# RHD2000_128_headstage.net
KiCad netlist of a schematic drawn in EAGLE
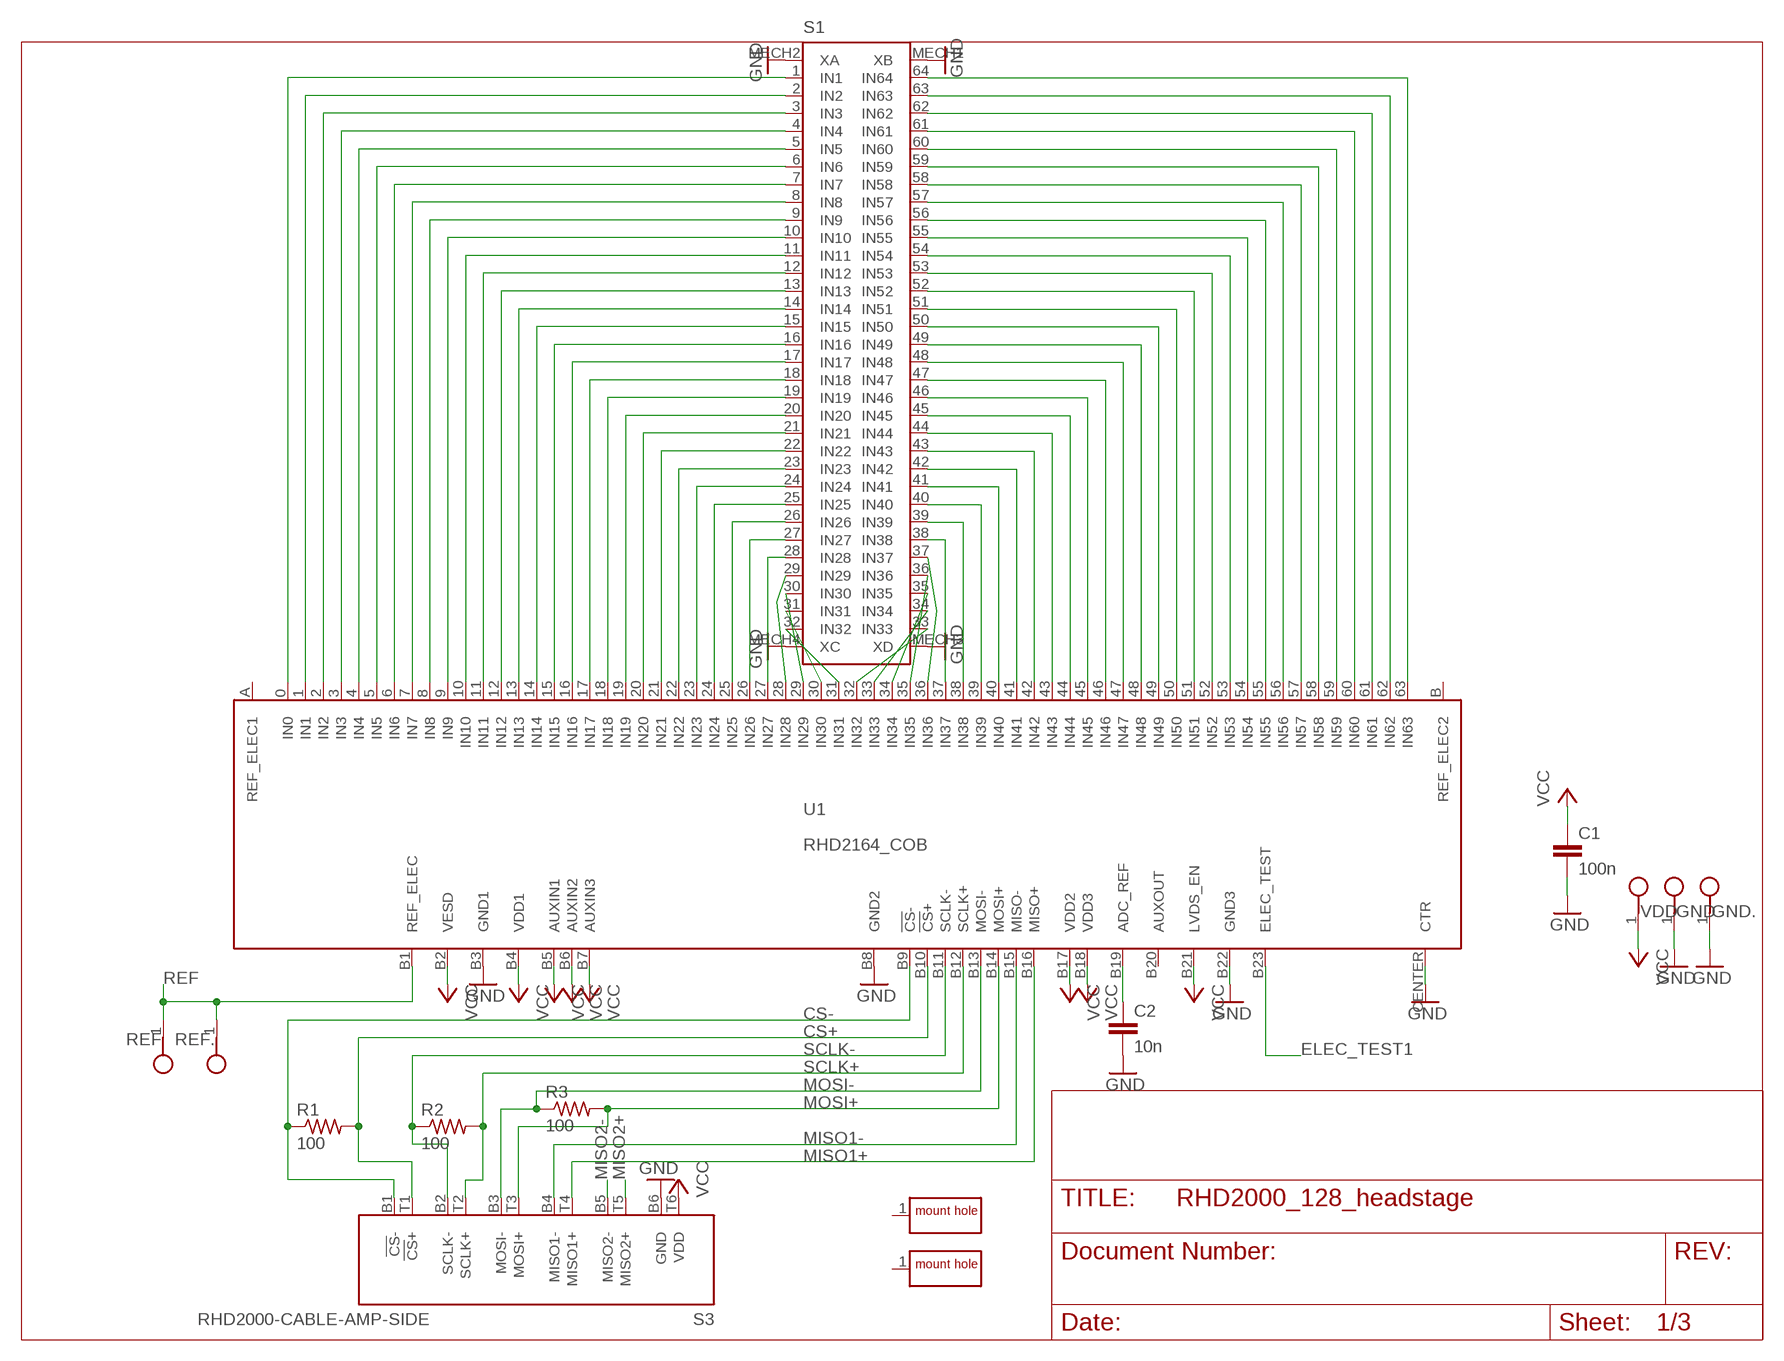
[diagram p0: schematic, sheet 1]
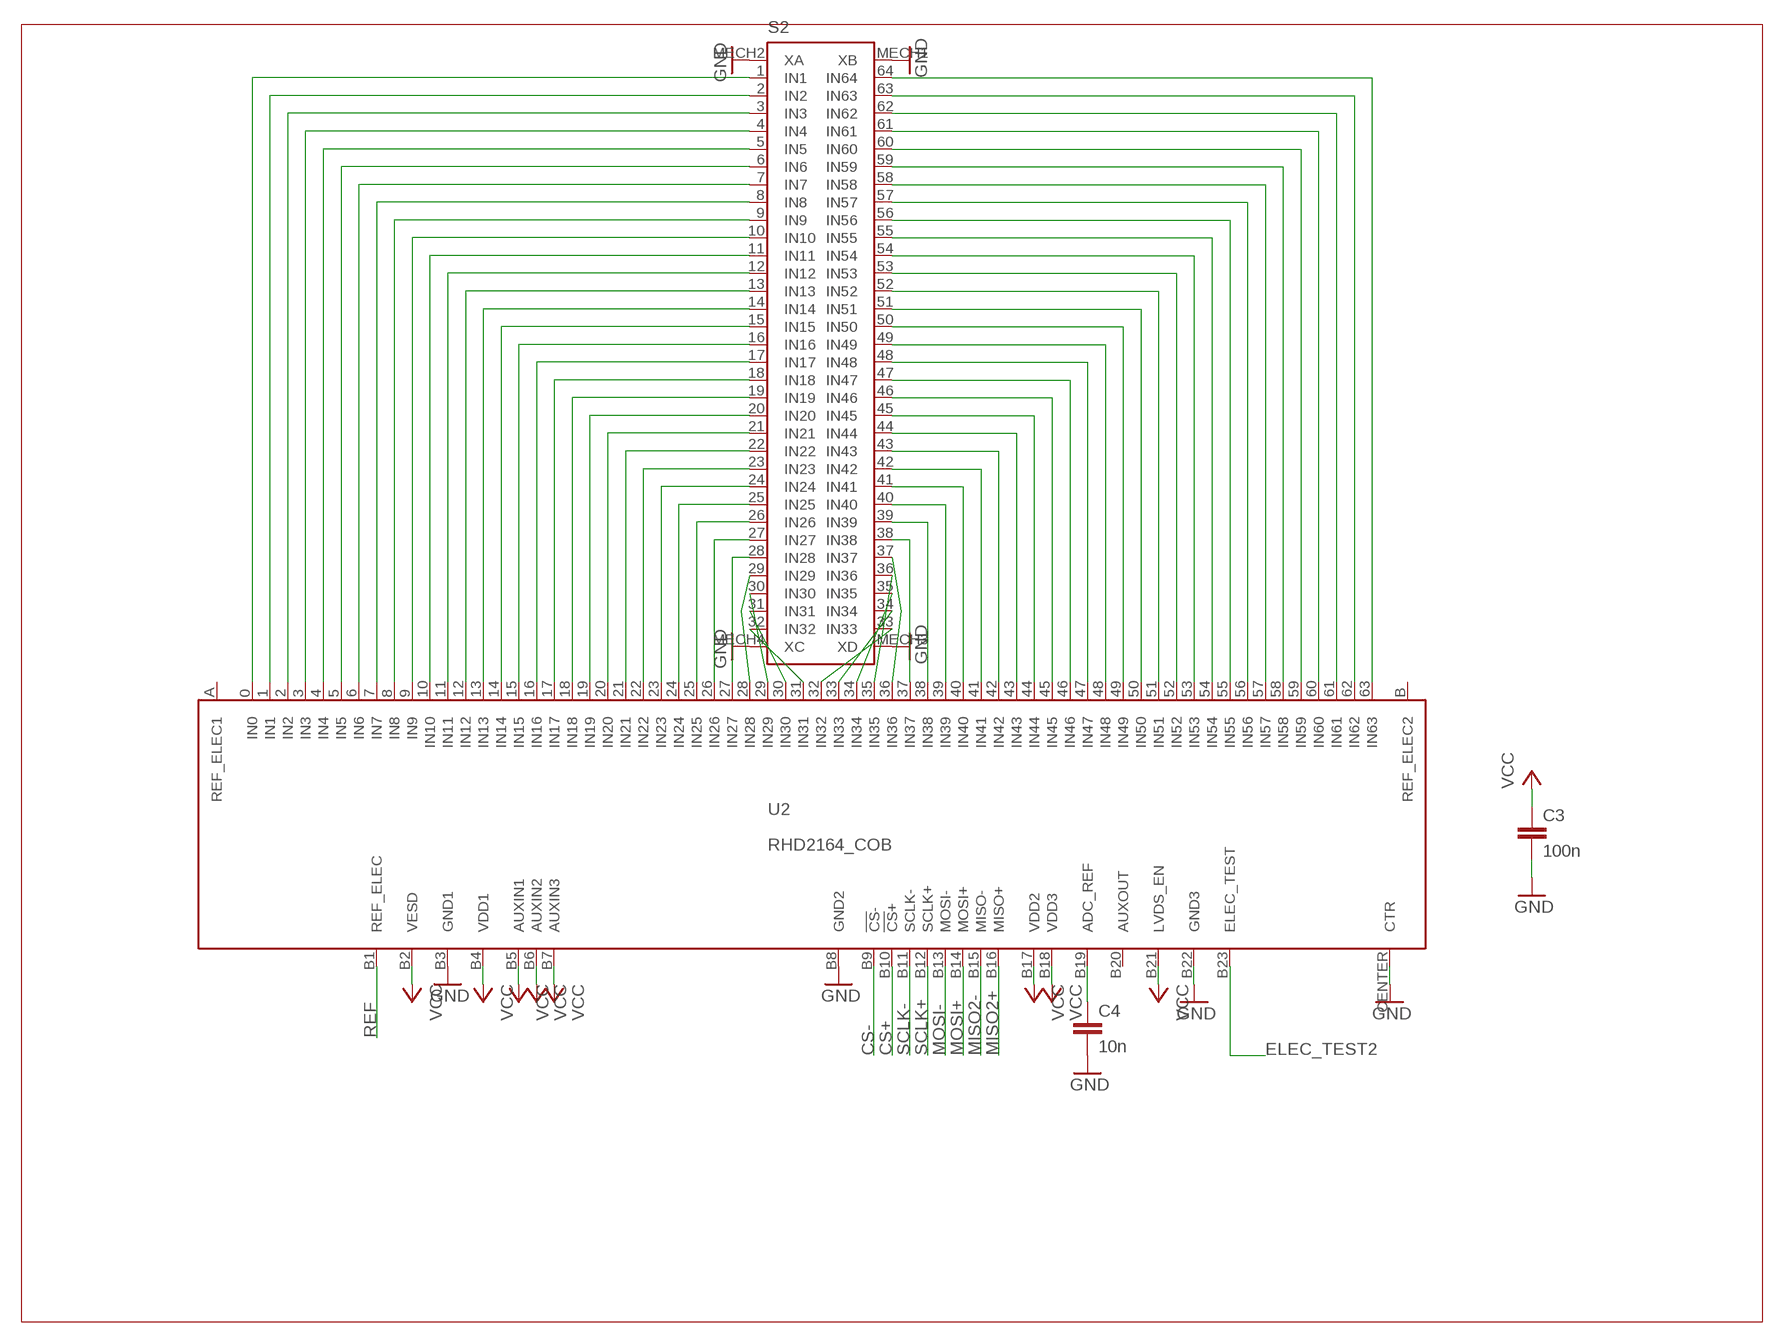
[diagram p1: schematic, sheet 2]
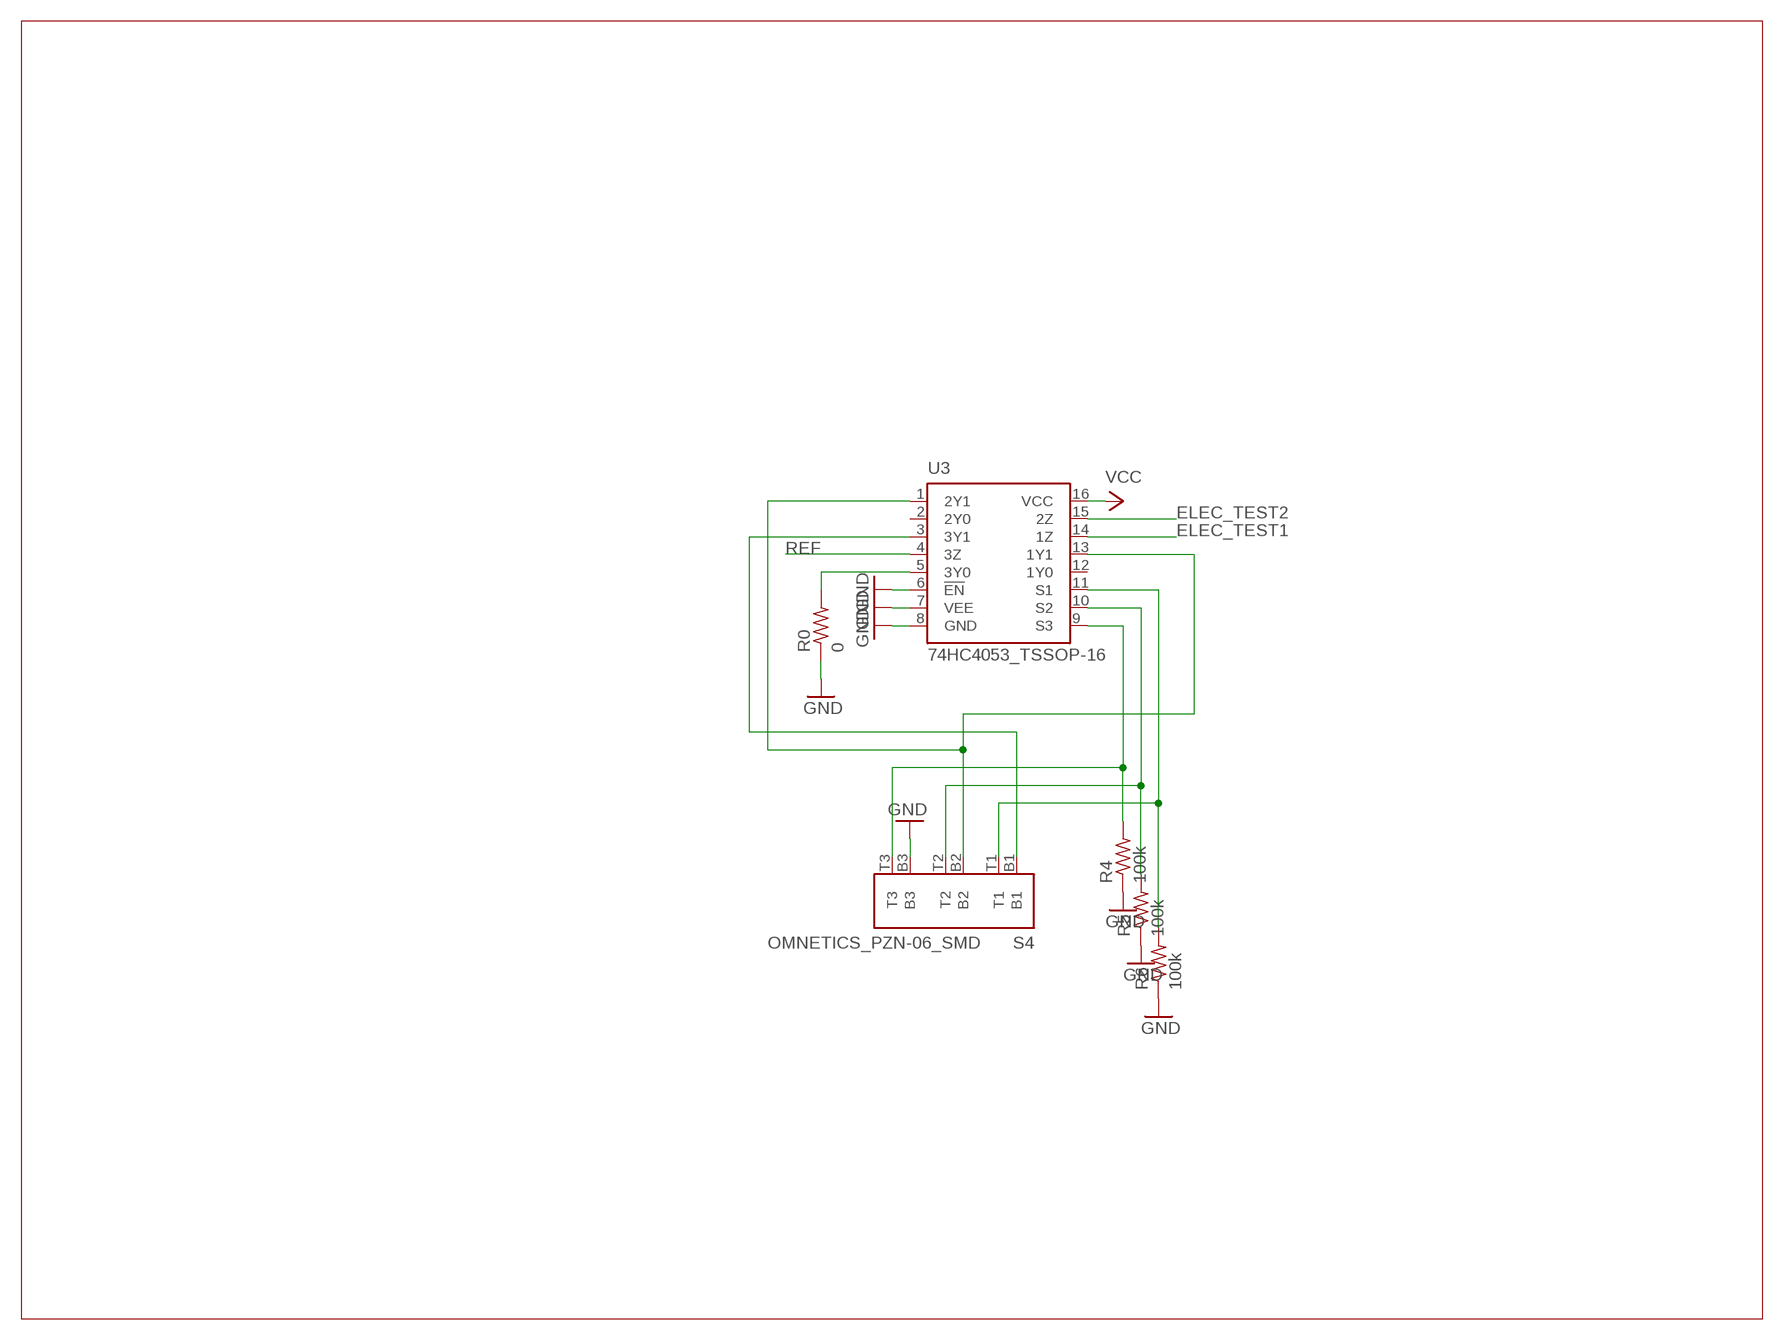
[diagram p2: schematic, sheet 3]

(export (version "E")
  (design (tool "Eeschema 10.0.6"))
  (components
    (comp (ref "C1")
      (value "100n")
      (footprint "eagle-import:0402")
      (libsource (lib "eagle-import") (part "C_0402"))
    )
    (comp (ref "C2")
      (value "10n")
      (footprint "eagle-import:0201")
      (libsource (lib "eagle-import") (part "C_0201"))
    )
    (comp (ref "GND")
      (value "TESTPOINT_SMALL")
      (footprint "eagle-import:TESTPOINT_SMALL")
      (libsource (lib "eagle-import") (part "TESTPOINT_SMALL"))
    )
    (comp (ref "GND.")
      (value "TESTPOINT_SMALL")
      (footprint "eagle-import:TESTPOINT_SMALL")
      (libsource (lib "eagle-import") (part "TESTPOINT_SMALL"))
    )
    (comp (ref "H1")
      (value "MOUNTING_HOLE_60MIL")
      (footprint "eagle-import:MOUNTING_HOLE_60MIL")
      (libsource (lib "eagle-import") (part "MOUNTING_HOLE_60MIL"))
    )
    (comp (ref "H2")
      (value "MOUNTING_HOLE_60MIL")
      (footprint "eagle-import:MOUNTING_HOLE_60MIL")
      (libsource (lib "eagle-import") (part "MOUNTING_HOLE_60MIL"))
    )
    (comp (ref "R1")
      (value "100")
      (footprint "eagle-import:0201")
      (libsource (lib "eagle-import") (part "R_0201"))
    )
    (comp (ref "R2")
      (value "100")
      (footprint "eagle-import:0201")
      (libsource (lib "eagle-import") (part "R_0201"))
    )
    (comp (ref "R3")
      (value "100")
      (footprint "eagle-import:0201")
      (libsource (lib "eagle-import") (part "R_0201"))
    )
    (comp (ref "REF")
      (value "TESTPOINT_SMALL")
      (footprint "eagle-import:TESTPOINT_SMALL")
      (libsource (lib "eagle-import") (part "TESTPOINT_SMALL"))
    )
    (comp (ref "REF.")
      (value "TESTPOINT_SMALL")
      (footprint "eagle-import:TESTPOINT_SMALL")
      (libsource (lib "eagle-import") (part "TESTPOINT_SMALL"))
    )
    (comp (ref "S1")
      (value "MOLEX_SLIMSTACK_64")
      (footprint "eagle-import:MOLEX_SLIMSTACK_64")
      (libsource (lib "eagle-import") (part "MOLEX_SLIMSTACK_64"))
    )
    (comp (ref "S3")
      (value "RHD2000-CABLE-AMP-SIDE")
      (footprint "eagle-import:OMNETICS_PZN-12-AA")
      (libsource (lib "eagle-import") (part "RHD2000-CABLE-AMP-SIDE"))
    )
    (comp (ref "U1")
      (value "RHD2164_COB")
      (footprint "eagle-import:RHD2164_COB")
      (libsource (lib "eagle-import") (part "RHD2164_COB"))
    )
    (comp (ref "VDD")
      (value "TESTPOINT_SMALL")
      (footprint "eagle-import:TESTPOINT_SMALL")
      (libsource (lib "eagle-import") (part "TESTPOINT_SMALL"))
    )
    (comp (ref "R0")
      (value "0")
      (footprint "eagle-import:0402")
      (libsource (lib "eagle-import") (part "R_0402"))
    )
    (comp (ref "R4")
      (value "100k")
      (footprint "eagle-import:0201")
      (libsource (lib "eagle-import") (part "R_0201"))
    )
    (comp (ref "R5")
      (value "100k")
      (footprint "eagle-import:0201")
      (libsource (lib "eagle-import") (part "R_0201"))
    )
    (comp (ref "R6")
      (value "100k")
      (footprint "eagle-import:0201")
      (libsource (lib "eagle-import") (part "R_0201"))
    )
    (comp (ref "S4")
      (value "OMNETICS_PZN-06_SMD")
      (footprint "eagle-import:OMNETICS_PZN-06-AA")
      (libsource (lib "eagle-import") (part "OMNETICS_PZN-06_SMD"))
    )
    (comp (ref "U3")
      (value "74HC4053_TSSOP-16")
      (footprint "eagle-import:TSSOP-16")
      (libsource (lib "eagle-import") (part "74HC4053_TSSOP-16"))
    )
    (comp (ref "C3")
      (value "100n")
      (footprint "eagle-import:0402")
      (libsource (lib "eagle-import") (part "C_0402"))
    )
    (comp (ref "C4")
      (value "10n")
      (footprint "eagle-import:0201")
      (libsource (lib "eagle-import") (part "C_0201"))
    )
    (comp (ref "S2")
      (value "MOLEX_SLIMSTACK_64")
      (footprint "eagle-import:MOLEX_SLIMSTACK_64")
      (libsource (lib "eagle-import") (part "MOLEX_SLIMSTACK_64"))
    )
    (comp (ref "U2")
      (value "RHD2164_COB")
      (footprint "eagle-import:RHD2164_COB")
      (libsource (lib "eagle-import") (part "RHD2164_COB"))
    )
  )
  (nets
    (net (code "1") (name "CS+") (class "Default")
      (node (ref "R1") (pin "2") (pinfunction "2_2") (pintype "passive"))
      (node (ref "S3") (pin "T1") (pinfunction "~{CS}+_T1") (pintype "bidirectional"))
      (node (ref "U1") (pin "B10") (pinfunction "~{CS}+_B10") (pintype "input"))
      (node (ref "U2") (pin "B10") (pinfunction "~{CS}+_B10") (pintype "input"))
    )
    (net (code "2") (name "CS-") (class "Default")
      (node (ref "R1") (pin "1") (pinfunction "1_1") (pintype "passive"))
      (node (ref "S3") (pin "B1") (pinfunction "~{CS}-_B1") (pintype "bidirectional"))
      (node (ref "U1") (pin "B9") (pinfunction "~{CS}-_B9") (pintype "input"))
      (node (ref "U2") (pin "B9") (pinfunction "~{CS}-_B9") (pintype "input"))
    )
    (net (code "3") (name "ELEC_TEST1") (class "Default")
      (node (ref "U1") (pin "B23") (pinfunction "ELEC_TEST_B23") (pintype "input"))
      (node (ref "U3") (pin "14") (pinfunction "1Z_14") (pintype "bidirectional"))
    )
    (net (code "4") (name "ELEC_TEST2") (class "Default")
      (node (ref "U2") (pin "B23") (pinfunction "ELEC_TEST_B23") (pintype "input"))
      (node (ref "U3") (pin "15") (pinfunction "2Z_15") (pintype "bidirectional"))
    )
    (net (code "5") (name "GND") (class "Default")
      (node (ref "C1") (pin "2") (pinfunction "2_2") (pintype "passive"))
      (node (ref "C2") (pin "2") (pinfunction "2_2") (pintype "passive"))
      (node (ref "C3") (pin "2") (pinfunction "2_2") (pintype "passive"))
      (node (ref "C4") (pin "2") (pinfunction "2_2") (pintype "passive"))
      (node (ref "GND") (pin "1") (pinfunction "1_1") (pintype "passive"))
      (node (ref "GND.") (pin "1") (pinfunction "1_1") (pintype "passive"))
      (node (ref "R0") (pin "1") (pinfunction "1_1") (pintype "passive"))
      (node (ref "R4") (pin "1") (pinfunction "1_1") (pintype "passive"))
      (node (ref "R5") (pin "1") (pinfunction "1_1") (pintype "passive"))
      (node (ref "R6") (pin "1") (pinfunction "1_1") (pintype "passive"))
      (node (ref "S1") (pin "MECH1") (pinfunction "XB_MECH1") (pintype "input"))
      (node (ref "S1") (pin "MECH2") (pinfunction "XA_MECH2") (pintype "input"))
      (node (ref "S1") (pin "MECH3") (pinfunction "XD_MECH3") (pintype "input"))
      (node (ref "S1") (pin "MECH4") (pinfunction "XC_MECH4") (pintype "input"))
      (node (ref "S2") (pin "MECH1") (pinfunction "XB_MECH1") (pintype "input"))
      (node (ref "S2") (pin "MECH2") (pinfunction "XA_MECH2") (pintype "input"))
      (node (ref "S2") (pin "MECH3") (pinfunction "XD_MECH3") (pintype "input"))
      (node (ref "S2") (pin "MECH4") (pinfunction "XC_MECH4") (pintype "input"))
      (node (ref "S3") (pin "B6") (pinfunction "GND_B6") (pintype "power_in"))
      (node (ref "S4") (pin "B3") (pinfunction "B3_B3") (pintype "bidirectional"))
      (node (ref "U1") (pin "B22") (pinfunction "GND3_B22") (pintype "power_in"))
      (node (ref "U1") (pin "B3") (pinfunction "GND1_B3") (pintype "power_in"))
      (node (ref "U1") (pin "B8") (pinfunction "GND2_B8") (pintype "power_in"))
      (node (ref "U1") (pin "CENTER") (pinfunction "CTR_CENTER") (pintype "power_in"))
      (node (ref "U2") (pin "B22") (pinfunction "GND3_B22") (pintype "power_in"))
      (node (ref "U2") (pin "B3") (pinfunction "GND1_B3") (pintype "power_in"))
      (node (ref "U2") (pin "B8") (pinfunction "GND2_B8") (pintype "power_in"))
      (node (ref "U2") (pin "CENTER") (pinfunction "CTR_CENTER") (pintype "power_in"))
      (node (ref "U3") (pin "6") (pinfunction "~{EN}_6") (pintype "input"))
      (node (ref "U3") (pin "7") (pinfunction "VEE_7") (pintype "power_in"))
      (node (ref "U3") (pin "8") (pinfunction "GND_8") (pintype "power_in"))
    )
    (net (code "6") (name "MISO1+") (class "Default")
      (node (ref "S3") (pin "T4") (pinfunction "MISO1+_T4") (pintype "bidirectional"))
      (node (ref "U1") (pin "B16") (pinfunction "MISO+_B16") (pintype "output"))
    )
    (net (code "7") (name "MISO1-") (class "Default")
      (node (ref "S3") (pin "B4") (pinfunction "MISO1-_B4") (pintype "bidirectional"))
      (node (ref "U1") (pin "B15") (pinfunction "MISO-_B15") (pintype "output"))
    )
    (net (code "8") (name "MISO2+") (class "Default")
      (node (ref "S3") (pin "T5") (pinfunction "MISO2+_T5") (pintype "bidirectional"))
      (node (ref "U2") (pin "B16") (pinfunction "MISO+_B16") (pintype "output"))
    )
    (net (code "9") (name "MISO2-") (class "Default")
      (node (ref "S3") (pin "B5") (pinfunction "MISO2-_B5") (pintype "bidirectional"))
      (node (ref "U2") (pin "B15") (pinfunction "MISO-_B15") (pintype "output"))
    )
    (net (code "10") (name "MOSI+") (class "Default")
      (node (ref "R3") (pin "2") (pinfunction "2_2") (pintype "passive"))
      (node (ref "S3") (pin "T3") (pinfunction "MOSI+_T3") (pintype "bidirectional"))
      (node (ref "U1") (pin "B14") (pinfunction "MOSI+_B14") (pintype "input"))
      (node (ref "U2") (pin "B14") (pinfunction "MOSI+_B14") (pintype "input"))
    )
    (net (code "11") (name "MOSI-") (class "Default")
      (node (ref "R3") (pin "1") (pinfunction "1_1") (pintype "passive"))
      (node (ref "S3") (pin "B3") (pinfunction "MOSI-_B3") (pintype "bidirectional"))
      (node (ref "U1") (pin "B13") (pinfunction "MOSI-_B13") (pintype "input"))
      (node (ref "U2") (pin "B13") (pinfunction "MOSI-_B13") (pintype "input"))
    )
    (net (code "12") (name "Net-(S1-IN1)") (class "Default")
      (node (ref "S1") (pin "1") (pinfunction "IN1_1") (pintype "input"))
      (node (ref "U1") (pin "0") (pinfunction "IN0_0") (pintype "input"))
    )
    (net (code "13") (name "Net-(S1-IN2)") (class "Default")
      (node (ref "S1") (pin "2") (pinfunction "IN2_2") (pintype "input"))
      (node (ref "U1") (pin "1") (pinfunction "IN1_1") (pintype "input"))
    )
    (net (code "14") (name "Net-(S1-IN3)") (class "Default")
      (node (ref "S1") (pin "3") (pinfunction "IN3_3") (pintype "input"))
      (node (ref "U1") (pin "2") (pinfunction "IN2_2") (pintype "input"))
    )
    (net (code "15") (name "Net-(S1-IN4)") (class "Default")
      (node (ref "S1") (pin "4") (pinfunction "IN4_4") (pintype "input"))
      (node (ref "U1") (pin "3") (pinfunction "IN3_3") (pintype "input"))
    )
    (net (code "16") (name "Net-(S1-IN5)") (class "Default")
      (node (ref "S1") (pin "5") (pinfunction "IN5_5") (pintype "input"))
      (node (ref "U1") (pin "4") (pinfunction "IN4_4") (pintype "input"))
    )
    (net (code "17") (name "Net-(S1-IN6)") (class "Default")
      (node (ref "S1") (pin "6") (pinfunction "IN6_6") (pintype "input"))
      (node (ref "U1") (pin "5") (pinfunction "IN5_5") (pintype "input"))
    )
    (net (code "18") (name "Net-(S1-IN7)") (class "Default")
      (node (ref "S1") (pin "7") (pinfunction "IN7_7") (pintype "input"))
      (node (ref "U1") (pin "6") (pinfunction "IN6_6") (pintype "input"))
    )
    (net (code "19") (name "Net-(S1-IN8)") (class "Default")
      (node (ref "S1") (pin "8") (pinfunction "IN8_8") (pintype "input"))
      (node (ref "U1") (pin "7") (pinfunction "IN7_7") (pintype "input"))
    )
    (net (code "20") (name "Net-(S1-IN9)") (class "Default")
      (node (ref "S1") (pin "9") (pinfunction "IN9_9") (pintype "input"))
      (node (ref "U1") (pin "8") (pinfunction "IN8_8") (pintype "input"))
    )
    (net (code "21") (name "Net-(S1-IN10)") (class "Default")
      (node (ref "S1") (pin "10") (pinfunction "IN10_10") (pintype "input"))
      (node (ref "U1") (pin "9") (pinfunction "IN9_9") (pintype "input"))
    )
    (net (code "22") (name "Net-(S1-IN11)") (class "Default")
      (node (ref "S1") (pin "11") (pinfunction "IN11_11") (pintype "input"))
      (node (ref "U1") (pin "10") (pinfunction "IN10_10") (pintype "input"))
    )
    (net (code "23") (name "Net-(S1-IN12)") (class "Default")
      (node (ref "S1") (pin "12") (pinfunction "IN12_12") (pintype "input"))
      (node (ref "U1") (pin "11") (pinfunction "IN11_11") (pintype "input"))
    )
    (net (code "24") (name "Net-(S1-IN13)") (class "Default")
      (node (ref "S1") (pin "13") (pinfunction "IN13_13") (pintype "input"))
      (node (ref "U1") (pin "12") (pinfunction "IN12_12") (pintype "input"))
    )
    (net (code "25") (name "Net-(S1-IN14)") (class "Default")
      (node (ref "S1") (pin "14") (pinfunction "IN14_14") (pintype "input"))
      (node (ref "U1") (pin "13") (pinfunction "IN13_13") (pintype "input"))
    )
    (net (code "26") (name "Net-(S1-IN15)") (class "Default")
      (node (ref "S1") (pin "15") (pinfunction "IN15_15") (pintype "input"))
      (node (ref "U1") (pin "14") (pinfunction "IN14_14") (pintype "input"))
    )
    (net (code "27") (name "Net-(S1-IN16)") (class "Default")
      (node (ref "S1") (pin "16") (pinfunction "IN16_16") (pintype "input"))
      (node (ref "U1") (pin "15") (pinfunction "IN15_15") (pintype "input"))
    )
    (net (code "28") (name "Net-(S1-IN17)") (class "Default")
      (node (ref "S1") (pin "17") (pinfunction "IN17_17") (pintype "input"))
      (node (ref "U1") (pin "16") (pinfunction "IN16_16") (pintype "input"))
    )
    (net (code "29") (name "Net-(S1-IN18)") (class "Default")
      (node (ref "S1") (pin "18") (pinfunction "IN18_18") (pintype "input"))
      (node (ref "U1") (pin "17") (pinfunction "IN17_17") (pintype "input"))
    )
    (net (code "30") (name "Net-(S1-IN19)") (class "Default")
      (node (ref "S1") (pin "19") (pinfunction "IN19_19") (pintype "input"))
      (node (ref "U1") (pin "18") (pinfunction "IN18_18") (pintype "input"))
    )
    (net (code "31") (name "Net-(S1-IN20)") (class "Default")
      (node (ref "S1") (pin "20") (pinfunction "IN20_20") (pintype "input"))
      (node (ref "U1") (pin "19") (pinfunction "IN19_19") (pintype "input"))
    )
    (net (code "32") (name "Net-(S1-IN21)") (class "Default")
      (node (ref "S1") (pin "21") (pinfunction "IN21_21") (pintype "input"))
      (node (ref "U1") (pin "20") (pinfunction "IN20_20") (pintype "input"))
    )
    (net (code "33") (name "Net-(S1-IN22)") (class "Default")
      (node (ref "S1") (pin "22") (pinfunction "IN22_22") (pintype "input"))
      (node (ref "U1") (pin "21") (pinfunction "IN21_21") (pintype "input"))
    )
    (net (code "34") (name "Net-(S1-IN23)") (class "Default")
      (node (ref "S1") (pin "23") (pinfunction "IN23_23") (pintype "input"))
      (node (ref "U1") (pin "22") (pinfunction "IN22_22") (pintype "input"))
    )
    (net (code "35") (name "Net-(S1-IN24)") (class "Default")
      (node (ref "S1") (pin "24") (pinfunction "IN24_24") (pintype "input"))
      (node (ref "U1") (pin "23") (pinfunction "IN23_23") (pintype "input"))
    )
    (net (code "36") (name "Net-(S1-IN25)") (class "Default")
      (node (ref "S1") (pin "25") (pinfunction "IN25_25") (pintype "input"))
      (node (ref "U1") (pin "24") (pinfunction "IN24_24") (pintype "input"))
    )
    (net (code "37") (name "Net-(S1-IN26)") (class "Default")
      (node (ref "S1") (pin "26") (pinfunction "IN26_26") (pintype "input"))
      (node (ref "U1") (pin "25") (pinfunction "IN25_25") (pintype "input"))
    )
    (net (code "38") (name "Net-(S1-IN27)") (class "Default")
      (node (ref "S1") (pin "27") (pinfunction "IN27_27") (pintype "input"))
      (node (ref "U1") (pin "26") (pinfunction "IN26_26") (pintype "input"))
    )
    (net (code "39") (name "Net-(S1-IN28)") (class "Default")
      (node (ref "S1") (pin "28") (pinfunction "IN28_28") (pintype "input"))
      (node (ref "U1") (pin "27") (pinfunction "IN27_27") (pintype "input"))
    )
    (net (code "40") (name "Net-(S1-IN29)") (class "Default")
      (node (ref "S1") (pin "29") (pinfunction "IN29_29") (pintype "input"))
      (node (ref "U1") (pin "28") (pinfunction "IN28_28") (pintype "input"))
    )
    (net (code "41") (name "Net-(S1-IN30)") (class "Default")
      (node (ref "S1") (pin "30") (pinfunction "IN30_30") (pintype "input"))
      (node (ref "U1") (pin "29") (pinfunction "IN29_29") (pintype "input"))
    )
    (net (code "42") (name "Net-(S1-IN31)") (class "Default")
      (node (ref "S1") (pin "31") (pinfunction "IN31_31") (pintype "input"))
      (node (ref "U1") (pin "30") (pinfunction "IN30_30") (pintype "input"))
    )
    (net (code "43") (name "Net-(S1-IN32)") (class "Default")
      (node (ref "S1") (pin "32") (pinfunction "IN32_32") (pintype "input"))
      (node (ref "U1") (pin "31") (pinfunction "IN31_31") (pintype "input"))
    )
    (net (code "44") (name "Net-(S1-IN33)") (class "Default")
      (node (ref "S1") (pin "33") (pinfunction "IN33_33") (pintype "input"))
      (node (ref "U1") (pin "32") (pinfunction "IN32_32") (pintype "input"))
    )
    (net (code "45") (name "Net-(S1-IN34)") (class "Default")
      (node (ref "S1") (pin "34") (pinfunction "IN34_34") (pintype "input"))
      (node (ref "U1") (pin "33") (pinfunction "IN33_33") (pintype "input"))
    )
    (net (code "46") (name "Net-(S1-IN35)") (class "Default")
      (node (ref "S1") (pin "35") (pinfunction "IN35_35") (pintype "input"))
      (node (ref "U1") (pin "34") (pinfunction "IN34_34") (pintype "input"))
    )
    (net (code "47") (name "Net-(S1-IN36)") (class "Default")
      (node (ref "S1") (pin "36") (pinfunction "IN36_36") (pintype "input"))
      (node (ref "U1") (pin "35") (pinfunction "IN35_35") (pintype "input"))
    )
    (net (code "48") (name "Net-(S1-IN37)") (class "Default")
      (node (ref "S1") (pin "37") (pinfunction "IN37_37") (pintype "input"))
      (node (ref "U1") (pin "36") (pinfunction "IN36_36") (pintype "input"))
    )
    (net (code "49") (name "Net-(S1-IN38)") (class "Default")
      (node (ref "S1") (pin "38") (pinfunction "IN38_38") (pintype "input"))
      (node (ref "U1") (pin "37") (pinfunction "IN37_37") (pintype "input"))
    )
    (net (code "50") (name "Net-(S1-IN39)") (class "Default")
      (node (ref "S1") (pin "39") (pinfunction "IN39_39") (pintype "input"))
      (node (ref "U1") (pin "38") (pinfunction "IN38_38") (pintype "input"))
    )
    (net (code "51") (name "Net-(S1-IN40)") (class "Default")
      (node (ref "S1") (pin "40") (pinfunction "IN40_40") (pintype "input"))
      (node (ref "U1") (pin "39") (pinfunction "IN39_39") (pintype "input"))
    )
    (net (code "52") (name "Net-(S1-IN41)") (class "Default")
      (node (ref "S1") (pin "41") (pinfunction "IN41_41") (pintype "input"))
      (node (ref "U1") (pin "40") (pinfunction "IN40_40") (pintype "input"))
    )
    (net (code "53") (name "Net-(S1-IN42)") (class "Default")
      (node (ref "S1") (pin "42") (pinfunction "IN42_42") (pintype "input"))
      (node (ref "U1") (pin "41") (pinfunction "IN41_41") (pintype "input"))
    )
    (net (code "54") (name "Net-(S1-IN43)") (class "Default")
      (node (ref "S1") (pin "43") (pinfunction "IN43_43") (pintype "input"))
      (node (ref "U1") (pin "42") (pinfunction "IN42_42") (pintype "input"))
    )
    (net (code "55") (name "Net-(S1-IN44)") (class "Default")
      (node (ref "S1") (pin "44") (pinfunction "IN44_44") (pintype "input"))
      (node (ref "U1") (pin "43") (pinfunction "IN43_43") (pintype "input"))
    )
    (net (code "56") (name "Net-(S1-IN45)") (class "Default")
      (node (ref "S1") (pin "45") (pinfunction "IN45_45") (pintype "input"))
      (node (ref "U1") (pin "44") (pinfunction "IN44_44") (pintype "input"))
    )
    (net (code "57") (name "Net-(S1-IN46)") (class "Default")
      (node (ref "S1") (pin "46") (pinfunction "IN46_46") (pintype "input"))
      (node (ref "U1") (pin "45") (pinfunction "IN45_45") (pintype "input"))
    )
    (net (code "58") (name "Net-(S1-IN47)") (class "Default")
      (node (ref "S1") (pin "47") (pinfunction "IN47_47") (pintype "input"))
      (node (ref "U1") (pin "46") (pinfunction "IN46_46") (pintype "input"))
    )
    (net (code "59") (name "Net-(S1-IN48)") (class "Default")
      (node (ref "S1") (pin "48") (pinfunction "IN48_48") (pintype "input"))
      (node (ref "U1") (pin "47") (pinfunction "IN47_47") (pintype "input"))
    )
    (net (code "60") (name "Net-(S1-IN49)") (class "Default")
      (node (ref "S1") (pin "49") (pinfunction "IN49_49") (pintype "input"))
      (node (ref "U1") (pin "48") (pinfunction "IN48_48") (pintype "input"))
    )
    (net (code "61") (name "Net-(S1-IN50)") (class "Default")
      (node (ref "S1") (pin "50") (pinfunction "IN50_50") (pintype "input"))
      (node (ref "U1") (pin "49") (pinfunction "IN49_49") (pintype "input"))
    )
    (net (code "62") (name "Net-(S1-IN51)") (class "Default")
      (node (ref "S1") (pin "51") (pinfunction "IN51_51") (pintype "input"))
      (node (ref "U1") (pin "50") (pinfunction "IN50_50") (pintype "input"))
    )
    (net (code "63") (name "Net-(S1-IN52)") (class "Default")
      (node (ref "S1") (pin "52") (pinfunction "IN52_52") (pintype "input"))
      (node (ref "U1") (pin "51") (pinfunction "IN51_51") (pintype "input"))
    )
    (net (code "64") (name "Net-(S1-IN53)") (class "Default")
      (node (ref "S1") (pin "53") (pinfunction "IN53_53") (pintype "input"))
      (node (ref "U1") (pin "52") (pinfunction "IN52_52") (pintype "input"))
    )
    (net (code "65") (name "Net-(S1-IN54)") (class "Default")
      (node (ref "S1") (pin "54") (pinfunction "IN54_54") (pintype "input"))
      (node (ref "U1") (pin "53") (pinfunction "IN53_53") (pintype "input"))
    )
    (net (code "66") (name "Net-(S1-IN55)") (class "Default")
      (node (ref "S1") (pin "55") (pinfunction "IN55_55") (pintype "input"))
      (node (ref "U1") (pin "54") (pinfunction "IN54_54") (pintype "input"))
    )
    (net (code "67") (name "Net-(S1-IN56)") (class "Default")
      (node (ref "S1") (pin "56") (pinfunction "IN56_56") (pintype "input"))
      (node (ref "U1") (pin "55") (pinfunction "IN55_55") (pintype "input"))
    )
    (net (code "68") (name "Net-(S1-IN57)") (class "Default")
      (node (ref "S1") (pin "57") (pinfunction "IN57_57") (pintype "input"))
      (node (ref "U1") (pin "56") (pinfunction "IN56_56") (pintype "input"))
    )
    (net (code "69") (name "Net-(S1-IN58)") (class "Default")
      (node (ref "S1") (pin "58") (pinfunction "IN58_58") (pintype "input"))
      (node (ref "U1") (pin "57") (pinfunction "IN57_57") (pintype "input"))
    )
    (net (code "70") (name "Net-(S1-IN59)") (class "Default")
      (node (ref "S1") (pin "59") (pinfunction "IN59_59") (pintype "input"))
      (node (ref "U1") (pin "58") (pinfunction "IN58_58") (pintype "input"))
    )
    (net (code "71") (name "Net-(S1-IN60)") (class "Default")
      (node (ref "S1") (pin "60") (pinfunction "IN60_60") (pintype "input"))
      (node (ref "U1") (pin "59") (pinfunction "IN59_59") (pintype "input"))
    )
    (net (code "72") (name "Net-(S1-IN61)") (class "Default")
      (node (ref "S1") (pin "61") (pinfunction "IN61_61") (pintype "input"))
      (node (ref "U1") (pin "60") (pinfunction "IN60_60") (pintype "input"))
    )
    (net (code "73") (name "Net-(S1-IN62)") (class "Default")
      (node (ref "S1") (pin "62") (pinfunction "IN62_62") (pintype "input"))
      (node (ref "U1") (pin "61") (pinfunction "IN61_61") (pintype "input"))
    )
    (net (code "74") (name "Net-(S1-IN63)") (class "Default")
      (node (ref "S1") (pin "63") (pinfunction "IN63_63") (pintype "input"))
      (node (ref "U1") (pin "62") (pinfunction "IN62_62") (pintype "input"))
    )
    (net (code "75") (name "Net-(S1-IN64)") (class "Default")
      (node (ref "S1") (pin "64") (pinfunction "IN64_64") (pintype "input"))
      (node (ref "U1") (pin "63") (pinfunction "IN63_63") (pintype "input"))
    )
    (net (code "76") (name "Net-(S2-IN1)") (class "Default")
      (node (ref "S2") (pin "1") (pinfunction "IN1_1") (pintype "input"))
      (node (ref "U2") (pin "0") (pinfunction "IN0_0") (pintype "input"))
    )
    (net (code "77") (name "Net-(S2-IN2)") (class "Default")
      (node (ref "S2") (pin "2") (pinfunction "IN2_2") (pintype "input"))
      (node (ref "U2") (pin "1") (pinfunction "IN1_1") (pintype "input"))
    )
    (net (code "78") (name "Net-(S2-IN3)") (class "Default")
      (node (ref "S2") (pin "3") (pinfunction "IN3_3") (pintype "input"))
      (node (ref "U2") (pin "2") (pinfunction "IN2_2") (pintype "input"))
    )
    (net (code "79") (name "Net-(S2-IN4)") (class "Default")
      (node (ref "S2") (pin "4") (pinfunction "IN4_4") (pintype "input"))
      (node (ref "U2") (pin "3") (pinfunction "IN3_3") (pintype "input"))
    )
    (net (code "80") (name "Net-(S2-IN5)") (class "Default")
      (node (ref "S2") (pin "5") (pinfunction "IN5_5") (pintype "input"))
      (node (ref "U2") (pin "4") (pinfunction "IN4_4") (pintype "input"))
    )
    (net (code "81") (name "Net-(S2-IN6)") (class "Default")
      (node (ref "S2") (pin "6") (pinfunction "IN6_6") (pintype "input"))
      (node (ref "U2") (pin "5") (pinfunction "IN5_5") (pintype "input"))
    )
    (net (code "82") (name "Net-(S2-IN7)") (class "Default")
      (node (ref "S2") (pin "7") (pinfunction "IN7_7") (pintype "input"))
      (node (ref "U2") (pin "6") (pinfunction "IN6_6") (pintype "input"))
    )
    (net (code "83") (name "Net-(S2-IN8)") (class "Default")
      (node (ref "S2") (pin "8") (pinfunction "IN8_8") (pintype "input"))
      (node (ref "U2") (pin "7") (pinfunction "IN7_7") (pintype "input"))
    )
    (net (code "84") (name "Net-(S2-IN9)") (class "Default")
      (node (ref "S2") (pin "9") (pinfunction "IN9_9") (pintype "input"))
      (node (ref "U2") (pin "8") (pinfunction "IN8_8") (pintype "input"))
    )
    (net (code "85") (name "Net-(S2-IN10)") (class "Default")
      (node (ref "S2") (pin "10") (pinfunction "IN10_10") (pintype "input"))
      (node (ref "U2") (pin "9") (pinfunction "IN9_9") (pintype "input"))
    )
    (net (code "86") (name "Net-(S2-IN11)") (class "Default")
      (node (ref "S2") (pin "11") (pinfunction "IN11_11") (pintype "input"))
      (node (ref "U2") (pin "10") (pinfunction "IN10_10") (pintype "input"))
    )
    (net (code "87") (name "Net-(S2-IN12)") (class "Default")
      (node (ref "S2") (pin "12") (pinfunction "IN12_12") (pintype "input"))
      (node (ref "U2") (pin "11") (pinfunction "IN11_11") (pintype "input"))
    )
    (net (code "88") (name "Net-(S2-IN13)") (class "Default")
      (node (ref "S2") (pin "13") (pinfunction "IN13_13") (pintype "input"))
      (node (ref "U2") (pin "12") (pinfunction "IN12_12") (pintype "input"))
    )
    (net (code "89") (name "Net-(S2-IN14)") (class "Default")
      (node (ref "S2") (pin "14") (pinfunction "IN14_14") (pintype "input"))
      (node (ref "U2") (pin "13") (pinfunction "IN13_13") (pintype "input"))
    )
    (net (code "90") (name "Net-(S2-IN15)") (class "Default")
      (node (ref "S2") (pin "15") (pinfunction "IN15_15") (pintype "input"))
      (node (ref "U2") (pin "14") (pinfunction "IN14_14") (pintype "input"))
    )
    (net (code "91") (name "Net-(S2-IN16)") (class "Default")
      (node (ref "S2") (pin "16") (pinfunction "IN16_16") (pintype "input"))
      (node (ref "U2") (pin "15") (pinfunction "IN15_15") (pintype "input"))
    )
    (net (code "92") (name "Net-(S2-IN17)") (class "Default")
      (node (ref "S2") (pin "17") (pinfunction "IN17_17") (pintype "input"))
      (node (ref "U2") (pin "16") (pinfunction "IN16_16") (pintype "input"))
    )
    (net (code "93") (name "Net-(S2-IN18)") (class "Default")
      (node (ref "S2") (pin "18") (pinfunction "IN18_18") (pintype "input"))
      (node (ref "U2") (pin "17") (pinfunction "IN17_17") (pintype "input"))
    )
    (net (code "94") (name "Net-(S2-IN19)") (class "Default")
      (node (ref "S2") (pin "19") (pinfunction "IN19_19") (pintype "input"))
      (node (ref "U2") (pin "18") (pinfunction "IN18_18") (pintype "input"))
    )
    (net (code "95") (name "Net-(S2-IN20)") (class "Default")
      (node (ref "S2") (pin "20") (pinfunction "IN20_20") (pintype "input"))
      (node (ref "U2") (pin "19") (pinfunction "IN19_19") (pintype "input"))
    )
    (net (code "96") (name "Net-(S2-IN21)") (class "Default")
      (node (ref "S2") (pin "21") (pinfunction "IN21_21") (pintype "input"))
      (node (ref "U2") (pin "20") (pinfunction "IN20_20") (pintype "input"))
    )
    (net (code "97") (name "Net-(S2-IN22)") (class "Default")
      (node (ref "S2") (pin "22") (pinfunction "IN22_22") (pintype "input"))
      (node (ref "U2") (pin "21") (pinfunction "IN21_21") (pintype "input"))
    )
    (net (code "98") (name "Net-(S2-IN23)") (class "Default")
      (node (ref "S2") (pin "23") (pinfunction "IN23_23") (pintype "input"))
      (node (ref "U2") (pin "22") (pinfunction "IN22_22") (pintype "input"))
    )
    (net (code "99") (name "Net-(S2-IN24)") (class "Default")
      (node (ref "S2") (pin "24") (pinfunction "IN24_24") (pintype "input"))
      (node (ref "U2") (pin "23") (pinfunction "IN23_23") (pintype "input"))
    )
    (net (code "100") (name "Net-(S2-IN25)") (class "Default")
      (node (ref "S2") (pin "25") (pinfunction "IN25_25") (pintype "input"))
      (node (ref "U2") (pin "24") (pinfunction "IN24_24") (pintype "input"))
    )
    (net (code "101") (name "Net-(S2-IN26)") (class "Default")
      (node (ref "S2") (pin "26") (pinfunction "IN26_26") (pintype "input"))
      (node (ref "U2") (pin "25") (pinfunction "IN25_25") (pintype "input"))
    )
    (net (code "102") (name "Net-(S2-IN27)") (class "Default")
      (node (ref "S2") (pin "27") (pinfunction "IN27_27") (pintype "input"))
      (node (ref "U2") (pin "26") (pinfunction "IN26_26") (pintype "input"))
    )
    (net (code "103") (name "Net-(S2-IN28)") (class "Default")
      (node (ref "S2") (pin "28") (pinfunction "IN28_28") (pintype "input"))
      (node (ref "U2") (pin "27") (pinfunction "IN27_27") (pintype "input"))
    )
    (net (code "104") (name "Net-(S2-IN29)") (class "Default")
      (node (ref "S2") (pin "29") (pinfunction "IN29_29") (pintype "input"))
      (node (ref "U2") (pin "28") (pinfunction "IN28_28") (pintype "input"))
    )
    (net (code "105") (name "Net-(S2-IN30)") (class "Default")
      (node (ref "S2") (pin "30") (pinfunction "IN30_30") (pintype "input"))
      (node (ref "U2") (pin "29") (pinfunction "IN29_29") (pintype "input"))
    )
    (net (code "106") (name "Net-(S2-IN31)") (class "Default")
      (node (ref "S2") (pin "31") (pinfunction "IN31_31") (pintype "input"))
      (node (ref "U2") (pin "30") (pinfunction "IN30_30") (pintype "input"))
    )
    (net (code "107") (name "Net-(S2-IN32)") (class "Default")
      (node (ref "S2") (pin "32") (pinfunction "IN32_32") (pintype "input"))
      (node (ref "U2") (pin "31") (pinfunction "IN31_31") (pintype "input"))
    )
    (net (code "108") (name "Net-(S2-IN33)") (class "Default")
      (node (ref "S2") (pin "33") (pinfunction "IN33_33") (pintype "input"))
      (node (ref "U2") (pin "32") (pinfunction "IN32_32") (pintype "input"))
    )
    (net (code "109") (name "Net-(S2-IN34)") (class "Default")
      (node (ref "S2") (pin "34") (pinfunction "IN34_34") (pintype "input"))
      (node (ref "U2") (pin "33") (pinfunction "IN33_33") (pintype "input"))
    )
    (net (code "110") (name "Net-(S2-IN35)") (class "Default")
      (node (ref "S2") (pin "35") (pinfunction "IN35_35") (pintype "input"))
      (node (ref "U2") (pin "34") (pinfunction "IN34_34") (pintype "input"))
    )
    (net (code "111") (name "Net-(S2-IN36)") (class "Default")
      (node (ref "S2") (pin "36") (pinfunction "IN36_36") (pintype "input"))
      (node (ref "U2") (pin "35") (pinfunction "IN35_35") (pintype "input"))
    )
    (net (code "112") (name "Net-(S2-IN37)") (class "Default")
      (node (ref "S2") (pin "37") (pinfunction "IN37_37") (pintype "input"))
      (node (ref "U2") (pin "36") (pinfunction "IN36_36") (pintype "input"))
    )
    (net (code "113") (name "Net-(S2-IN38)") (class "Default")
      (node (ref "S2") (pin "38") (pinfunction "IN38_38") (pintype "input"))
      (node (ref "U2") (pin "37") (pinfunction "IN37_37") (pintype "input"))
    )
    (net (code "114") (name "Net-(S2-IN39)") (class "Default")
      (node (ref "S2") (pin "39") (pinfunction "IN39_39") (pintype "input"))
      (node (ref "U2") (pin "38") (pinfunction "IN38_38") (pintype "input"))
    )
    (net (code "115") (name "Net-(S2-IN40)") (class "Default")
      (node (ref "S2") (pin "40") (pinfunction "IN40_40") (pintype "input"))
      (node (ref "U2") (pin "39") (pinfunction "IN39_39") (pintype "input"))
    )
    (net (code "116") (name "Net-(S2-IN41)") (class "Default")
      (node (ref "S2") (pin "41") (pinfunction "IN41_41") (pintype "input"))
      (node (ref "U2") (pin "40") (pinfunction "IN40_40") (pintype "input"))
    )
    (net (code "117") (name "Net-(S2-IN42)") (class "Default")
      (node (ref "S2") (pin "42") (pinfunction "IN42_42") (pintype "input"))
      (node (ref "U2") (pin "41") (pinfunction "IN41_41") (pintype "input"))
    )
    (net (code "118") (name "Net-(S2-IN43)") (class "Default")
      (node (ref "S2") (pin "43") (pinfunction "IN43_43") (pintype "input"))
      (node (ref "U2") (pin "42") (pinfunction "IN42_42") (pintype "input"))
    )
    (net (code "119") (name "Net-(S2-IN44)") (class "Default")
      (node (ref "S2") (pin "44") (pinfunction "IN44_44") (pintype "input"))
      (node (ref "U2") (pin "43") (pinfunction "IN43_43") (pintype "input"))
    )
    (net (code "120") (name "Net-(S2-IN45)") (class "Default")
      (node (ref "S2") (pin "45") (pinfunction "IN45_45") (pintype "input"))
      (node (ref "U2") (pin "44") (pinfunction "IN44_44") (pintype "input"))
    )
    (net (code "121") (name "Net-(S2-IN46)") (class "Default")
      (node (ref "S2") (pin "46") (pinfunction "IN46_46") (pintype "input"))
      (node (ref "U2") (pin "45") (pinfunction "IN45_45") (pintype "input"))
    )
    (net (code "122") (name "Net-(S2-IN47)") (class "Default")
      (node (ref "S2") (pin "47") (pinfunction "IN47_47") (pintype "input"))
      (node (ref "U2") (pin "46") (pinfunction "IN46_46") (pintype "input"))
    )
    (net (code "123") (name "Net-(S2-IN48)") (class "Default")
      (node (ref "S2") (pin "48") (pinfunction "IN48_48") (pintype "input"))
      (node (ref "U2") (pin "47") (pinfunction "IN47_47") (pintype "input"))
    )
    (net (code "124") (name "Net-(S2-IN49)") (class "Default")
      (node (ref "S2") (pin "49") (pinfunction "IN49_49") (pintype "input"))
      (node (ref "U2") (pin "48") (pinfunction "IN48_48") (pintype "input"))
    )
    (net (code "125") (name "Net-(S2-IN50)") (class "Default")
      (node (ref "S2") (pin "50") (pinfunction "IN50_50") (pintype "input"))
      (node (ref "U2") (pin "49") (pinfunction "IN49_49") (pintype "input"))
    )
    (net (code "126") (name "Net-(S2-IN51)") (class "Default")
      (node (ref "S2") (pin "51") (pinfunction "IN51_51") (pintype "input"))
      (node (ref "U2") (pin "50") (pinfunction "IN50_50") (pintype "input"))
    )
    (net (code "127") (name "Net-(S2-IN52)") (class "Default")
      (node (ref "S2") (pin "52") (pinfunction "IN52_52") (pintype "input"))
      (node (ref "U2") (pin "51") (pinfunction "IN51_51") (pintype "input"))
    )
    (net (code "128") (name "Net-(S2-IN53)") (class "Default")
      (node (ref "S2") (pin "53") (pinfunction "IN53_53") (pintype "input"))
      (node (ref "U2") (pin "52") (pinfunction "IN52_52") (pintype "input"))
    )
    (net (code "129") (name "Net-(S2-IN54)") (class "Default")
      (node (ref "S2") (pin "54") (pinfunction "IN54_54") (pintype "input"))
      (node (ref "U2") (pin "53") (pinfunction "IN53_53") (pintype "input"))
    )
    (net (code "130") (name "Net-(S2-IN55)") (class "Default")
      (node (ref "S2") (pin "55") (pinfunction "IN55_55") (pintype "input"))
      (node (ref "U2") (pin "54") (pinfunction "IN54_54") (pintype "input"))
    )
    (net (code "131") (name "Net-(S2-IN56)") (class "Default")
      (node (ref "S2") (pin "56") (pinfunction "IN56_56") (pintype "input"))
      (node (ref "U2") (pin "55") (pinfunction "IN55_55") (pintype "input"))
    )
    (net (code "132") (name "Net-(S2-IN57)") (class "Default")
      (node (ref "S2") (pin "57") (pinfunction "IN57_57") (pintype "input"))
      (node (ref "U2") (pin "56") (pinfunction "IN56_56") (pintype "input"))
    )
    (net (code "133") (name "Net-(S2-IN58)") (class "Default")
      (node (ref "S2") (pin "58") (pinfunction "IN58_58") (pintype "input"))
      (node (ref "U2") (pin "57") (pinfunction "IN57_57") (pintype "input"))
    )
    (net (code "134") (name "Net-(S2-IN59)") (class "Default")
      (node (ref "S2") (pin "59") (pinfunction "IN59_59") (pintype "input"))
      (node (ref "U2") (pin "58") (pinfunction "IN58_58") (pintype "input"))
    )
    (net (code "135") (name "Net-(S2-IN60)") (class "Default")
      (node (ref "S2") (pin "60") (pinfunction "IN60_60") (pintype "input"))
      (node (ref "U2") (pin "59") (pinfunction "IN59_59") (pintype "input"))
    )
    (net (code "136") (name "Net-(S2-IN61)") (class "Default")
      (node (ref "S2") (pin "61") (pinfunction "IN61_61") (pintype "input"))
      (node (ref "U2") (pin "60") (pinfunction "IN60_60") (pintype "input"))
    )
    (net (code "137") (name "Net-(S2-IN62)") (class "Default")
      (node (ref "S2") (pin "62") (pinfunction "IN62_62") (pintype "input"))
      (node (ref "U2") (pin "61") (pinfunction "IN61_61") (pintype "input"))
    )
    (net (code "138") (name "Net-(S2-IN63)") (class "Default")
      (node (ref "S2") (pin "63") (pinfunction "IN63_63") (pintype "input"))
      (node (ref "U2") (pin "62") (pinfunction "IN62_62") (pintype "input"))
    )
    (net (code "139") (name "Net-(S2-IN64)") (class "Default")
      (node (ref "S2") (pin "64") (pinfunction "IN64_64") (pintype "input"))
      (node (ref "U2") (pin "63") (pinfunction "IN63_63") (pintype "input"))
    )
    (net (code "140") (name "Net-(U1-ADC_REF)") (class "Default")
      (node (ref "C2") (pin "1") (pinfunction "1_1") (pintype "passive"))
      (node (ref "U1") (pin "B19") (pinfunction "ADC_REF_B19") (pintype "passive"))
    )
    (net (code "141") (name "Net-(U2-ADC_REF)") (class "Default")
      (node (ref "C4") (pin "1") (pinfunction "1_1") (pintype "passive"))
      (node (ref "U2") (pin "B19") (pinfunction "ADC_REF_B19") (pintype "passive"))
    )
    (net (code "142") (name "Net-(U3-1Y1)") (class "Default")
      (node (ref "S4") (pin "B2") (pinfunction "B2_B2") (pintype "bidirectional"))
      (node (ref "U3") (pin "1") (pinfunction "2Y1_1") (pintype "bidirectional"))
      (node (ref "U3") (pin "13") (pinfunction "1Y1_13") (pintype "bidirectional"))
    )
    (net (code "143") (name "Net-(U3-3Y0)") (class "Default")
      (node (ref "R0") (pin "2") (pinfunction "2_2") (pintype "passive"))
      (node (ref "U3") (pin "5") (pinfunction "3Y0_5") (pintype "bidirectional"))
    )
    (net (code "144") (name "Net-(U3-3Y1)") (class "Default")
      (node (ref "S4") (pin "B1") (pinfunction "B1_B1") (pintype "bidirectional"))
      (node (ref "U3") (pin "3") (pinfunction "3Y1_3") (pintype "bidirectional"))
    )
    (net (code "145") (name "Net-(U3-S1)") (class "Default")
      (node (ref "R6") (pin "2") (pinfunction "2_2") (pintype "passive"))
      (node (ref "S4") (pin "T1") (pinfunction "T1_T1") (pintype "bidirectional"))
      (node (ref "U3") (pin "11") (pinfunction "S1_11") (pintype "input"))
    )
    (net (code "146") (name "Net-(U3-S2)") (class "Default")
      (node (ref "R5") (pin "2") (pinfunction "2_2") (pintype "passive"))
      (node (ref "S4") (pin "T2") (pinfunction "T2_T2") (pintype "bidirectional"))
      (node (ref "U3") (pin "10") (pinfunction "S2_10") (pintype "input"))
    )
    (net (code "147") (name "Net-(U3-S3)") (class "Default")
      (node (ref "R4") (pin "2") (pinfunction "2_2") (pintype "passive"))
      (node (ref "S4") (pin "T3") (pinfunction "T3_T3") (pintype "bidirectional"))
      (node (ref "U3") (pin "9") (pinfunction "S3_9") (pintype "input"))
    )
    (net (code "148") (name "REF") (class "Default")
      (node (ref "REF") (pin "1") (pinfunction "1_1") (pintype "passive"))
      (node (ref "REF.") (pin "1") (pinfunction "1_1") (pintype "passive"))
      (node (ref "U1") (pin "B1") (pinfunction "REF_ELEC_B1") (pintype "input"))
      (node (ref "U2") (pin "B1") (pinfunction "REF_ELEC_B1") (pintype "input"))
      (node (ref "U3") (pin "4") (pinfunction "3Z_4") (pintype "bidirectional"))
    )
    (net (code "149") (name "SCLK+") (class "Default")
      (node (ref "R2") (pin "2") (pinfunction "2_2") (pintype "passive"))
      (node (ref "S3") (pin "T2") (pinfunction "SCLK+_T2") (pintype "bidirectional"))
      (node (ref "U1") (pin "B12") (pinfunction "SCLK+_B12") (pintype "input"))
      (node (ref "U2") (pin "B12") (pinfunction "SCLK+_B12") (pintype "input"))
    )
    (net (code "150") (name "SCLK-") (class "Default")
      (node (ref "R2") (pin "1") (pinfunction "1_1") (pintype "passive"))
      (node (ref "S3") (pin "B2") (pinfunction "SCLK-_B2") (pintype "bidirectional"))
      (node (ref "U1") (pin "B11") (pinfunction "SCLK-_B11") (pintype "input"))
      (node (ref "U2") (pin "B11") (pinfunction "SCLK-_B11") (pintype "input"))
    )
    (net (code "151") (name "VCC") (class "Default")
      (node (ref "C1") (pin "1") (pinfunction "1_1") (pintype "passive"))
      (node (ref "C3") (pin "1") (pinfunction "1_1") (pintype "passive"))
      (node (ref "S3") (pin "T6") (pinfunction "VDD_T6") (pintype "bidirectional"))
      (node (ref "U1") (pin "B17") (pinfunction "VDD2_B17") (pintype "power_in"))
      (node (ref "U1") (pin "B18") (pinfunction "VDD3_B18") (pintype "power_in"))
      (node (ref "U1") (pin "B2") (pinfunction "VESD_B2") (pintype "power_in"))
      (node (ref "U1") (pin "B21") (pinfunction "LVDS_EN_B21") (pintype "input"))
      (node (ref "U1") (pin "B4") (pinfunction "VDD1_B4") (pintype "power_in"))
      (node (ref "U1") (pin "B5") (pinfunction "AUXIN1_B5") (pintype "input"))
      (node (ref "U1") (pin "B6") (pinfunction "AUXIN2_B6") (pintype "input"))
      (node (ref "U1") (pin "B7") (pinfunction "AUXIN3_B7") (pintype "input"))
      (node (ref "U2") (pin "B17") (pinfunction "VDD2_B17") (pintype "power_in"))
      (node (ref "U2") (pin "B18") (pinfunction "VDD3_B18") (pintype "power_in"))
      (node (ref "U2") (pin "B2") (pinfunction "VESD_B2") (pintype "power_in"))
      (node (ref "U2") (pin "B21") (pinfunction "LVDS_EN_B21") (pintype "input"))
      (node (ref "U2") (pin "B4") (pinfunction "VDD1_B4") (pintype "power_in"))
      (node (ref "U2") (pin "B5") (pinfunction "AUXIN1_B5") (pintype "input"))
      (node (ref "U2") (pin "B6") (pinfunction "AUXIN2_B6") (pintype "input"))
      (node (ref "U2") (pin "B7") (pinfunction "AUXIN3_B7") (pintype "input"))
      (node (ref "U3") (pin "16") (pinfunction "VCC_16") (pintype "power_in"))
      (node (ref "VDD") (pin "1") (pinfunction "1_1") (pintype "passive"))
    )
    (net (code "152") (name "unconnected-(H1-Pad1)") (class "Default")
      (node (ref "H1") (pin "1") (pinfunction "1_1") (pintype "passive"))
    )
    (net (code "153") (name "unconnected-(H2-Pad1)") (class "Default")
      (node (ref "H2") (pin "1") (pinfunction "1_1") (pintype "passive"))
    )
    (net (code "154") (name "unconnected-(U1-AUXOUT-PadB20)") (class "Default")
      (node (ref "U1") (pin "B20") (pinfunction "AUXOUT_B20") (pintype "tri_state"))
    )
    (net (code "155") (name "unconnected-(U1-REF_ELEC1-PadA)") (class "Default")
      (node (ref "U1") (pin "A") (pinfunction "REF_ELEC1_A") (pintype "input"))
    )
    (net (code "156") (name "unconnected-(U1-REF_ELEC2-PadB)") (class "Default")
      (node (ref "U1") (pin "B") (pinfunction "REF_ELEC2_B") (pintype "input"))
    )
    (net (code "157") (name "unconnected-(U2-AUXOUT-PadB20)") (class "Default")
      (node (ref "U2") (pin "B20") (pinfunction "AUXOUT_B20") (pintype "tri_state"))
    )
    (net (code "158") (name "unconnected-(U2-REF_ELEC1-PadA)") (class "Default")
      (node (ref "U2") (pin "A") (pinfunction "REF_ELEC1_A") (pintype "input"))
    )
    (net (code "159") (name "unconnected-(U2-REF_ELEC2-PadB)") (class "Default")
      (node (ref "U2") (pin "B") (pinfunction "REF_ELEC2_B") (pintype "input"))
    )
    (net (code "160") (name "unconnected-(U3-1Y0-Pad12)") (class "Default")
      (node (ref "U3") (pin "12") (pinfunction "1Y0_12") (pintype "bidirectional"))
    )
    (net (code "161") (name "unconnected-(U3-2Y0-Pad2)") (class "Default")
      (node (ref "U3") (pin "2") (pinfunction "2Y0_2") (pintype "bidirectional"))
    )
  )
)
